# sheet.net
KiCad netlist of a schematic drawn in EasyEDA
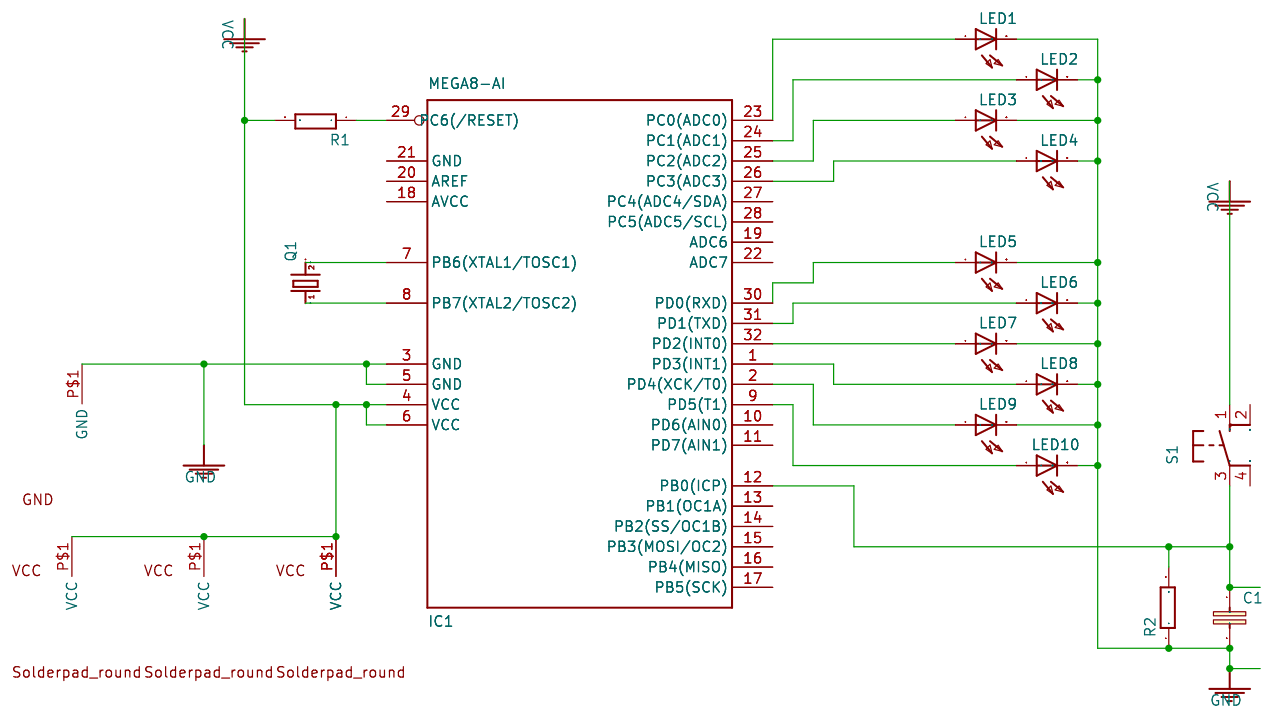
[diagram p0: schematic sheet]

(export (version "E")
  (design (tool "Eeschema 10.0.6"))
  (components
    (comp (ref "C1") (value "C-EUC0805") (libsource (lib "") (part "Unknown_610_-55")))
    (comp (ref "IC1") (value "MEGA8-AI") (libsource (lib "") (part "Unknown_285_-195")))
    (comp (ref "LED1") (value "LEDCHIP-LED0805") (libsource (lib "") (part "Unknown_485_-335")))
    (comp (ref "LED2") (value "LEDCHIP-LED0805") (libsource (lib "") (part "Unknown_515_-315")))
    (comp (ref "LED3") (value "LEDCHIP-LED0805") (libsource (lib "") (part "Unknown_485_-295")))
    (comp (ref "LED4") (value "LEDCHIP-LED0805") (libsource (lib "") (part "Unknown_515_-275")))
    (comp (ref "LED5") (value "LEDCHIP-LED0805") (libsource (lib "") (part "Unknown_485_-225")))
    (comp (ref "LED6") (value "LEDCHIP-LED0805") (libsource (lib "") (part "Unknown_515_-205")))
    (comp (ref "LED7") (value "LEDCHIP-LED0805") (libsource (lib "") (part "Unknown_485_-185")))
    (comp (ref "LED8") (value "LEDCHIP-LED0805") (libsource (lib "") (part "Unknown_515_-165")))
    (comp (ref "LED9") (value "LEDCHIP-LED0805") (libsource (lib "") (part "Unknown_485_-145")))
    (comp (ref "LED10") (value "LEDCHIP-LED0805") (libsource (lib "") (part "Unknown_515_-125")))
    (comp (ref "Q1") (value "CRYSTALTC26H") (libsource (lib "") (part "Unknown_155_-215")))
    (comp (ref "R1") (value "R-EU_R0805") (libsource (lib "") (part "Unknown_160_-295")))
    (comp (ref "R2") (value "R-EU_R0805") (libsource (lib "") (part "Unknown_580_-55")))
    (comp (ref "S1") (value "10-XX") (libsource (lib "") (part "Unknown_610_-135")))
    (comp (ref "U$1") (value "VCC_PLATE") (libsource (lib "") (part "Unknown_170_-50")))
    (comp (ref "U$2") (value "VCC_PLATE") (libsource (lib "") (part "Unknown_105_-50")))
    (comp (ref "U$3") (value "GND_PLATE") (libsource (lib "") (part "Unknown_45_-135")))
    (comp (ref "U$4") (value "VCC_PLATE") (libsource (lib "") (part "Unknown_40_-50")))
  )
  (nets
    (net (code "1") (name "GND") (class "Default")
      (node (ref "C1") (pin "2") (pinfunction "2_2") (pintype "bidirectional"))
      (node (ref "IC1") (pin "3") (pinfunction "GND_3") (pintype "bidirectional"))
      (node (ref "IC1") (pin "5") (pinfunction "GND_5") (pintype "bidirectional"))
      (node (ref "LED1") (pin "C") (pinfunction "C_C") (pintype "bidirectional"))
      (node (ref "LED10") (pin "C") (pinfunction "C_C") (pintype "bidirectional"))
      (node (ref "LED2") (pin "C") (pinfunction "C_C") (pintype "bidirectional"))
      (node (ref "LED3") (pin "C") (pinfunction "C_C") (pintype "bidirectional"))
      (node (ref "LED4") (pin "C") (pinfunction "C_C") (pintype "bidirectional"))
      (node (ref "LED5") (pin "C") (pinfunction "C_C") (pintype "bidirectional"))
      (node (ref "LED6") (pin "C") (pinfunction "C_C") (pintype "bidirectional"))
      (node (ref "LED7") (pin "C") (pinfunction "C_C") (pintype "bidirectional"))
      (node (ref "LED8") (pin "C") (pinfunction "C_C") (pintype "bidirectional"))
      (node (ref "LED9") (pin "C") (pinfunction "C_C") (pintype "bidirectional"))
      (node (ref "R2") (pin "1") (pinfunction "1_1") (pintype "bidirectional"))
      (node (ref "U$3") (pin "P$1") (pinfunction "GND_P$1") (pintype "bidirectional"))
    )
    (net (code "2") (name "Net-(IC1-PB0(ICP))") (class "Default")
      (node (ref "C1") (pin "1") (pinfunction "1_1") (pintype "bidirectional"))
      (node (ref "IC1") (pin "12") (pinfunction "PB0(ICP)_12") (pintype "bidirectional"))
      (node (ref "R2") (pin "2") (pinfunction "2_2") (pintype "bidirectional"))
      (node (ref "S1") (pin "3") (pinfunction "P_3") (pintype "bidirectional"))
    )
    (net (code "3") (name "Net-(IC1-PB6(XTAL1{slash}TOSC1))") (class "Default")
      (node (ref "IC1") (pin "7") (pinfunction "PB6(XTAL1/TOSC1)_7") (pintype "bidirectional"))
      (node (ref "Q1") (pin "2") (pinfunction "2_2") (pintype "bidirectional"))
    )
    (net (code "4") (name "Net-(IC1-PB7(XTAL2{slash}TOSC2))") (class "Default")
      (node (ref "IC1") (pin "8") (pinfunction "PB7(XTAL2/TOSC2)_8") (pintype "bidirectional"))
      (node (ref "Q1") (pin "1") (pinfunction "1_1") (pintype "bidirectional"))
    )
    (net (code "5") (name "Net-(IC1-PC0(ADC0))") (class "Default")
      (node (ref "IC1") (pin "23") (pinfunction "PC0(ADC0)_23") (pintype "bidirectional"))
      (node (ref "LED1") (pin "A") (pinfunction "A_A") (pintype "bidirectional"))
    )
    (net (code "6") (name "Net-(IC1-PC1(ADC1))") (class "Default")
      (node (ref "IC1") (pin "24") (pinfunction "PC1(ADC1)_24") (pintype "bidirectional"))
      (node (ref "LED2") (pin "A") (pinfunction "A_A") (pintype "bidirectional"))
    )
    (net (code "7") (name "Net-(IC1-PC2(ADC2))") (class "Default")
      (node (ref "IC1") (pin "25") (pinfunction "PC2(ADC2)_25") (pintype "bidirectional"))
      (node (ref "LED3") (pin "A") (pinfunction "A_A") (pintype "bidirectional"))
    )
    (net (code "8") (name "Net-(IC1-PC3(ADC3))") (class "Default")
      (node (ref "IC1") (pin "26") (pinfunction "PC3(ADC3)_26") (pintype "bidirectional"))
      (node (ref "LED4") (pin "A") (pinfunction "A_A") (pintype "bidirectional"))
    )
    (net (code "9") (name "Net-(IC1-PC6({slash}RESET))") (class "Default")
      (node (ref "IC1") (pin "29") (pinfunction "PC6(/RESET)_29") (pintype "bidirectional"))
      (node (ref "R1") (pin "1") (pinfunction "1_1") (pintype "bidirectional"))
    )
    (net (code "10") (name "Net-(IC1-PD0(RXD))") (class "Default")
      (node (ref "IC1") (pin "30") (pinfunction "PD0(RXD)_30") (pintype "bidirectional"))
      (node (ref "LED5") (pin "A") (pinfunction "A_A") (pintype "bidirectional"))
    )
    (net (code "11") (name "Net-(IC1-PD1(TXD))") (class "Default")
      (node (ref "IC1") (pin "31") (pinfunction "PD1(TXD)_31") (pintype "bidirectional"))
      (node (ref "LED6") (pin "A") (pinfunction "A_A") (pintype "bidirectional"))
    )
    (net (code "12") (name "Net-(IC1-PD2(INT0))") (class "Default")
      (node (ref "IC1") (pin "32") (pinfunction "PD2(INT0)_32") (pintype "bidirectional"))
      (node (ref "LED7") (pin "A") (pinfunction "A_A") (pintype "bidirectional"))
    )
    (net (code "13") (name "Net-(IC1-PD3(INT1))") (class "Default")
      (node (ref "IC1") (pin "1") (pinfunction "PD3(INT1)_1") (pintype "bidirectional"))
      (node (ref "LED8") (pin "A") (pinfunction "A_A") (pintype "bidirectional"))
    )
    (net (code "14") (name "Net-(IC1-PD4(XCK{slash}T0))") (class "Default")
      (node (ref "IC1") (pin "2") (pinfunction "PD4(XCK/T0)_2") (pintype "bidirectional"))
      (node (ref "LED9") (pin "A") (pinfunction "A_A") (pintype "bidirectional"))
    )
    (net (code "15") (name "Net-(IC1-PD5(T1))") (class "Default")
      (node (ref "IC1") (pin "9") (pinfunction "PD5(T1)_9") (pintype "bidirectional"))
      (node (ref "LED10") (pin "A") (pinfunction "A_A") (pintype "bidirectional"))
    )
    (net (code "16") (name "VCC") (class "Default")
      (node (ref "IC1") (pin "4") (pinfunction "VCC_4") (pintype "bidirectional"))
      (node (ref "IC1") (pin "6") (pinfunction "VCC_6") (pintype "bidirectional"))
      (node (ref "R1") (pin "2") (pinfunction "2_2") (pintype "bidirectional"))
      (node (ref "S1") (pin "1") (pinfunction "S_1") (pintype "bidirectional"))
      (node (ref "U$1") (pin "P$1") (pinfunction "VCC_P$1") (pintype "bidirectional"))
      (node (ref "U$2") (pin "P$1") (pinfunction "VCC_P$1") (pintype "bidirectional"))
      (node (ref "U$4") (pin "P$1") (pinfunction "VCC_P$1") (pintype "bidirectional"))
    )
    (net (code "17") (name "unconnected-(IC1-ADC6-Pad19)") (class "Default")
      (node (ref "IC1") (pin "19") (pinfunction "ADC6_19") (pintype "bidirectional"))
    )
    (net (code "18") (name "unconnected-(IC1-ADC7-Pad22)") (class "Default")
      (node (ref "IC1") (pin "22") (pinfunction "ADC7_22") (pintype "bidirectional"))
    )
    (net (code "19") (name "unconnected-(IC1-AREF-Pad20)") (class "Default")
      (node (ref "IC1") (pin "20") (pinfunction "AREF_20") (pintype "bidirectional"))
    )
    (net (code "20") (name "unconnected-(IC1-AVCC-Pad18)") (class "Default")
      (node (ref "IC1") (pin "18") (pinfunction "AVCC_18") (pintype "bidirectional"))
    )
    (net (code "21") (name "unconnected-(IC1-GND-Pad21)") (class "Default")
      (node (ref "IC1") (pin "21") (pinfunction "GND_21") (pintype "bidirectional"))
    )
    (net (code "22") (name "unconnected-(IC1-PB1(OC1A)-Pad13)") (class "Default")
      (node (ref "IC1") (pin "13") (pinfunction "PB1(OC1A)_13") (pintype "bidirectional"))
    )
    (net (code "23") (name "unconnected-(IC1-PB2(SS{slash}OC1B)-Pad14)") (class "Default")
      (node (ref "IC1") (pin "14") (pinfunction "PB2(SS/OC1B)_14") (pintype "bidirectional"))
    )
    (net (code "24") (name "unconnected-(IC1-PB3(MOSI{slash}OC2)-Pad15)") (class "Default")
      (node (ref "IC1") (pin "15") (pinfunction "PB3(MOSI/OC2)_15") (pintype "bidirectional"))
    )
    (net (code "25") (name "unconnected-(IC1-PB4(MISO)-Pad16)") (class "Default")
      (node (ref "IC1") (pin "16") (pinfunction "PB4(MISO)_16") (pintype "bidirectional"))
    )
    (net (code "26") (name "unconnected-(IC1-PB5(SCK)-Pad17)") (class "Default")
      (node (ref "IC1") (pin "17") (pinfunction "PB5(SCK)_17") (pintype "bidirectional"))
    )
    (net (code "27") (name "unconnected-(IC1-PC4(ADC4{slash}SDA)-Pad27)") (class "Default")
      (node (ref "IC1") (pin "27") (pinfunction "PC4(ADC4/SDA)_27") (pintype "bidirectional"))
    )
    (net (code "28") (name "unconnected-(IC1-PC5(ADC5{slash}SCL)-Pad28)") (class "Default")
      (node (ref "IC1") (pin "28") (pinfunction "PC5(ADC5/SCL)_28") (pintype "bidirectional"))
    )
    (net (code "29") (name "unconnected-(IC1-PD6(AIN0)-Pad10)") (class "Default")
      (node (ref "IC1") (pin "10") (pinfunction "PD6(AIN0)_10") (pintype "bidirectional"))
    )
    (net (code "30") (name "unconnected-(IC1-PD7(AIN1)-Pad11)") (class "Default")
      (node (ref "IC1") (pin "11") (pinfunction "PD7(AIN1)_11") (pintype "bidirectional"))
    )
    (net (code "31") (name "unconnected-(S1-P1-Pad4)") (class "Default")
      (node (ref "S1") (pin "4") (pinfunction "P1_4") (pintype "bidirectional"))
    )
    (net (code "32") (name "unconnected-(S1-S1-Pad2)") (class "Default")
      (node (ref "S1") (pin "2") (pinfunction "S1_2") (pintype "bidirectional"))
    )
  )
)
